# Plugs.net
KiCad netlist of a schematic drawn in Altium Designer
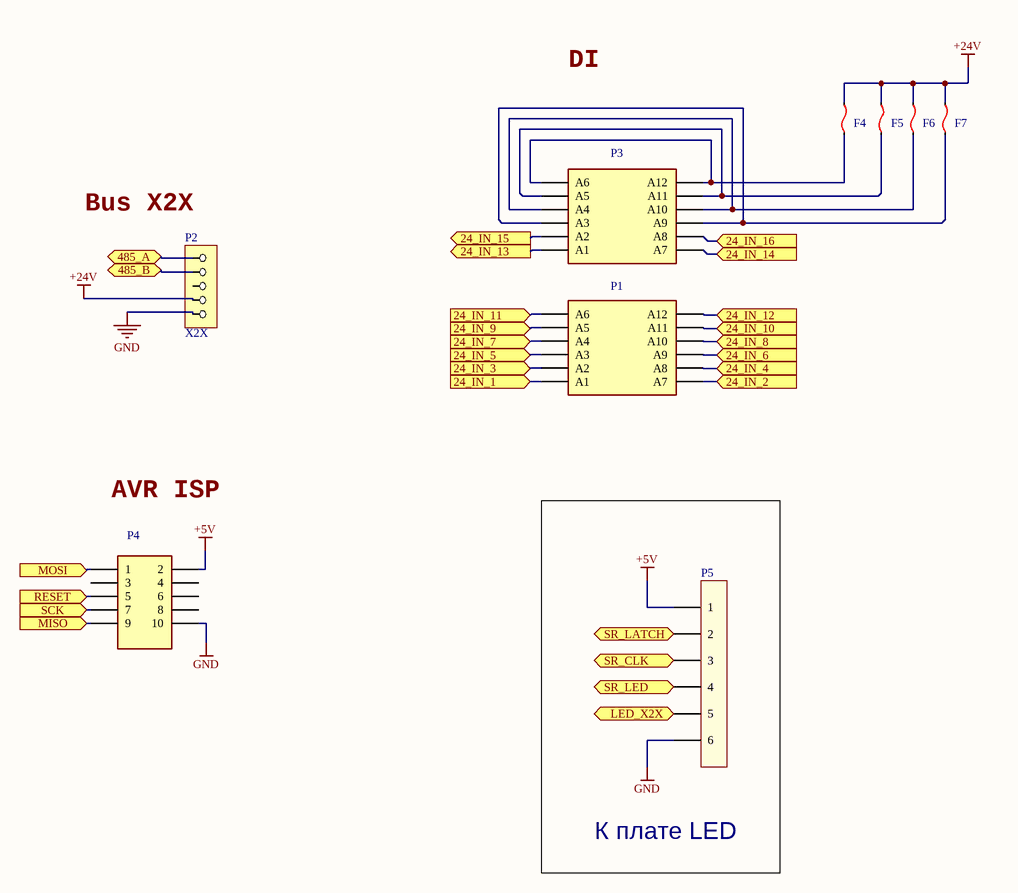
[diagram p0: Plugs.SchDoc]

(export (version "E")
  (design (tool "Eeschema 10.0.6"))
  (components
    (comp (ref "F4")
      (value "Fuse PTS")
      (footprint "1210_MF")
      (fields (field (name "PART NUMBER") "MF-MSMF010-2"))
      (libsource (lib "МЦТР.00010592.00.002") (part "MSMF"))
    )
    (comp (ref "F5")
      (value "Fuse PTS")
      (footprint "1210_MF")
      (fields (field (name "PART NUMBER") "MF-MSMF010-2"))
      (libsource (lib "МЦТР.00010592.00.002") (part "MSMF"))
    )
    (comp (ref "F6")
      (value "Fuse PTS")
      (footprint "1210_MF")
      (fields (field (name "PART NUMBER") "MF-MSMF010-2"))
      (libsource (lib "МЦТР.00010592.00.002") (part "MSMF"))
    )
    (comp (ref "F7")
      (value "Fuse PTS")
      (footprint "1210_MF")
      (fields (field (name "PART NUMBER") "MF-MSMF010-2"))
      (libsource (lib "МЦТР.00010592.00.002") (part "MSMF"))
    )
    (comp (ref "P1")
      (value "MCD 1.5/6 Phoenix")
      (footprint "МЦТР.00010592.00.002:mcd 1,5/6-G1-3.81")
      (libsource (lib "kontr") (part "MCD 1.5/6 Phoenix"))
    )
    (comp (ref "P2")
      (value "X2X")
      (footprint "MSTBA 1757271")
      (fields (field (name "PART NUMBER") "EMSTBA 2.5/5-G-5.08"))
      (libsource (lib "kontr") (part "EMSTBA 2.5/5-G-5.08"))
    )
    (comp (ref "P3")
      (value "~")
      (footprint "МЦТР.00010592.00.002:mcd 1,5/6-G1-3.81")
      (fields (field (name "PART NUMBER") "MCD 1.5/6 Phoenix"))
      (libsource (lib "kontr") (part "MCD 1.5/6 Phoenix"))
    )
    (comp (ref "P4")
      (value "~")
      (footprint "IDC-10MS")
      (fields (field (name "PART NUMBER") "DS1013-10SSIB1-B-0"))
      (libsource (lib "kontr") (part "IDC-10MS"))
    )
    (comp (ref "P5")
      (value "~")
      (footprint "МЦТР.00010592.00.002:PLS-6 2.54")
      (fields (field (name "PART NUMBER") "PLS-6"))
      (libsource (lib "levin") (part "PLS-6"))
    )
  )
  (nets
    (net (code "1") (name "+5V") (class "Default")
      (node (ref "P4") (pin "2") (pinfunction "2_2") (pintype "passive"))
      (node (ref "P5") (pin "1") (pinfunction "1_1") (pintype "passive"))
    )
    (net (code "2") (name "+24V") (class "Default")
      (node (ref "F4") (pin "1") (pinfunction "1_1") (pintype "passive"))
      (node (ref "F5") (pin "1") (pinfunction "1_1") (pintype "passive"))
      (node (ref "F6") (pin "1") (pinfunction "1_1") (pintype "passive"))
      (node (ref "F7") (pin "1") (pinfunction "1_1") (pintype "passive"))
      (node (ref "P2") (pin "4") (pinfunction "2_4") (pintype "passive"))
    )
    (net (code "3") (name "/24_IN_1") (class "Default")
      (node (ref "P1") (pin "11") (pinfunction "A1_11") (pintype "passive"))
    )
    (net (code "4") (name "/24_IN_2") (class "Default")
      (node (ref "P1") (pin "12") (pinfunction "A7_12") (pintype "passive"))
    )
    (net (code "5") (name "/24_IN_3") (class "Default")
      (node (ref "P1") (pin "9") (pinfunction "A2_9") (pintype "passive"))
    )
    (net (code "6") (name "/24_IN_4") (class "Default")
      (node (ref "P1") (pin "10") (pinfunction "A8_10") (pintype "passive"))
    )
    (net (code "7") (name "/24_IN_5") (class "Default")
      (node (ref "P1") (pin "7") (pinfunction "A3_7") (pintype "passive"))
    )
    (net (code "8") (name "/24_IN_6") (class "Default")
      (node (ref "P1") (pin "8") (pinfunction "A9_8") (pintype "passive"))
    )
    (net (code "9") (name "/24_IN_7") (class "Default")
      (node (ref "P1") (pin "5") (pinfunction "A4_5") (pintype "passive"))
    )
    (net (code "10") (name "/24_IN_8") (class "Default")
      (node (ref "P1") (pin "6") (pinfunction "A10_6") (pintype "passive"))
    )
    (net (code "11") (name "/24_IN_9") (class "Default")
      (node (ref "P1") (pin "3") (pinfunction "A5_3") (pintype "passive"))
    )
    (net (code "12") (name "/24_IN_10") (class "Default")
      (node (ref "P1") (pin "4") (pinfunction "A11_4") (pintype "passive"))
    )
    (net (code "13") (name "/24_IN_11") (class "Default")
      (node (ref "P1") (pin "1") (pinfunction "A6_1") (pintype "passive"))
    )
    (net (code "14") (name "/24_IN_12") (class "Default")
      (node (ref "P1") (pin "2") (pinfunction "A12_2") (pintype "passive"))
    )
    (net (code "15") (name "/24_IN_13") (class "Default")
      (node (ref "P3") (pin "11") (pinfunction "A1_11") (pintype "passive"))
    )
    (net (code "16") (name "/24_IN_14") (class "Default")
      (node (ref "P3") (pin "12") (pinfunction "A7_12") (pintype "passive"))
    )
    (net (code "17") (name "/24_IN_15") (class "Default")
      (node (ref "P3") (pin "9") (pinfunction "A2_9") (pintype "passive"))
    )
    (net (code "18") (name "/24_IN_16") (class "Default")
      (node (ref "P3") (pin "10") (pinfunction "A8_10") (pintype "passive"))
    )
    (net (code "19") (name "/485_A") (class "Default")
      (node (ref "P2") (pin "1") (pinfunction "1_1") (pintype "passive"))
    )
    (net (code "20") (name "/485_B") (class "Default")
      (node (ref "P2") (pin "2") (pinfunction "2_2") (pintype "passive"))
    )
    (net (code "21") (name "/LED_X2X") (class "Default")
      (node (ref "P5") (pin "5") (pinfunction "5_5") (pintype "passive"))
    )
    (net (code "22") (name "/MISO") (class "Default")
      (node (ref "P4") (pin "9") (pinfunction "9_9") (pintype "passive"))
    )
    (net (code "23") (name "/MOSI") (class "Default")
      (node (ref "P4") (pin "1") (pinfunction "1_1") (pintype "passive"))
    )
    (net (code "24") (name "/RESET") (class "Default")
      (node (ref "P4") (pin "5") (pinfunction "5_5") (pintype "passive"))
    )
    (net (code "25") (name "/SCK") (class "Default")
      (node (ref "P4") (pin "7") (pinfunction "7_7") (pintype "passive"))
    )
    (net (code "26") (name "/SR_CLK") (class "Default")
      (node (ref "P5") (pin "3") (pinfunction "3_3") (pintype "passive"))
    )
    (net (code "27") (name "/SR_LATCH") (class "Default")
      (node (ref "P5") (pin "2") (pinfunction "2_2") (pintype "passive"))
    )
    (net (code "28") (name "/SR_LED") (class "Default")
      (node (ref "P5") (pin "4") (pinfunction "4_4") (pintype "passive"))
    )
    (net (code "29") (name "GND") (class "Default")
      (node (ref "P2") (pin "5") (pinfunction "3_5") (pintype "passive"))
      (node (ref "P4") (pin "10") (pinfunction "10_10") (pintype "passive"))
      (node (ref "P5") (pin "6") (pinfunction "6_6") (pintype "passive"))
    )
    (net (code "30") (name "Net-(P3-A3)") (class "Default")
      (node (ref "F7") (pin "2") (pinfunction "2_2") (pintype "passive"))
      (node (ref "P3") (pin "7") (pinfunction "A3_7") (pintype "passive"))
      (node (ref "P3") (pin "8") (pinfunction "A9_8") (pintype "passive"))
    )
    (net (code "31") (name "Net-(P3-A10)") (class "Default")
      (node (ref "F6") (pin "2") (pinfunction "2_2") (pintype "passive"))
      (node (ref "P3") (pin "5") (pinfunction "A4_5") (pintype "passive"))
      (node (ref "P3") (pin "6") (pinfunction "A10_6") (pintype "passive"))
    )
    (net (code "32") (name "Net-(P3-A11)") (class "Default")
      (node (ref "F5") (pin "2") (pinfunction "2_2") (pintype "passive"))
      (node (ref "P3") (pin "3") (pinfunction "A5_3") (pintype "passive"))
      (node (ref "P3") (pin "4") (pinfunction "A11_4") (pintype "passive"))
    )
    (net (code "33") (name "Net-(P3-A12)") (class "Default")
      (node (ref "F4") (pin "2") (pinfunction "2_2") (pintype "passive"))
      (node (ref "P3") (pin "1") (pinfunction "A6_1") (pintype "passive"))
      (node (ref "P3") (pin "2") (pinfunction "A12_2") (pintype "passive"))
    )
    (net (code "34") (name "unconnected-(P2-Pad3)") (class "Default")
      (node (ref "P2") (pin "3") (pinfunction "3_3") (pintype "passive"))
    )
    (net (code "35") (name "unconnected-(P4-Pad3)") (class "Default")
      (node (ref "P4") (pin "3") (pinfunction "3_3") (pintype "passive"))
    )
    (net (code "36") (name "unconnected-(P4-Pad4)") (class "Default")
      (node (ref "P4") (pin "4") (pinfunction "4_4") (pintype "passive"))
    )
    (net (code "37") (name "unconnected-(P4-Pad6)") (class "Default")
      (node (ref "P4") (pin "6") (pinfunction "6_6") (pintype "passive"))
    )
    (net (code "38") (name "unconnected-(P4-Pad8)") (class "Default")
      (node (ref "P4") (pin "8") (pinfunction "8_8") (pintype "passive"))
    )
  )
)
